# Sheet1.net
KiCad netlist of a schematic drawn in Altium Designer
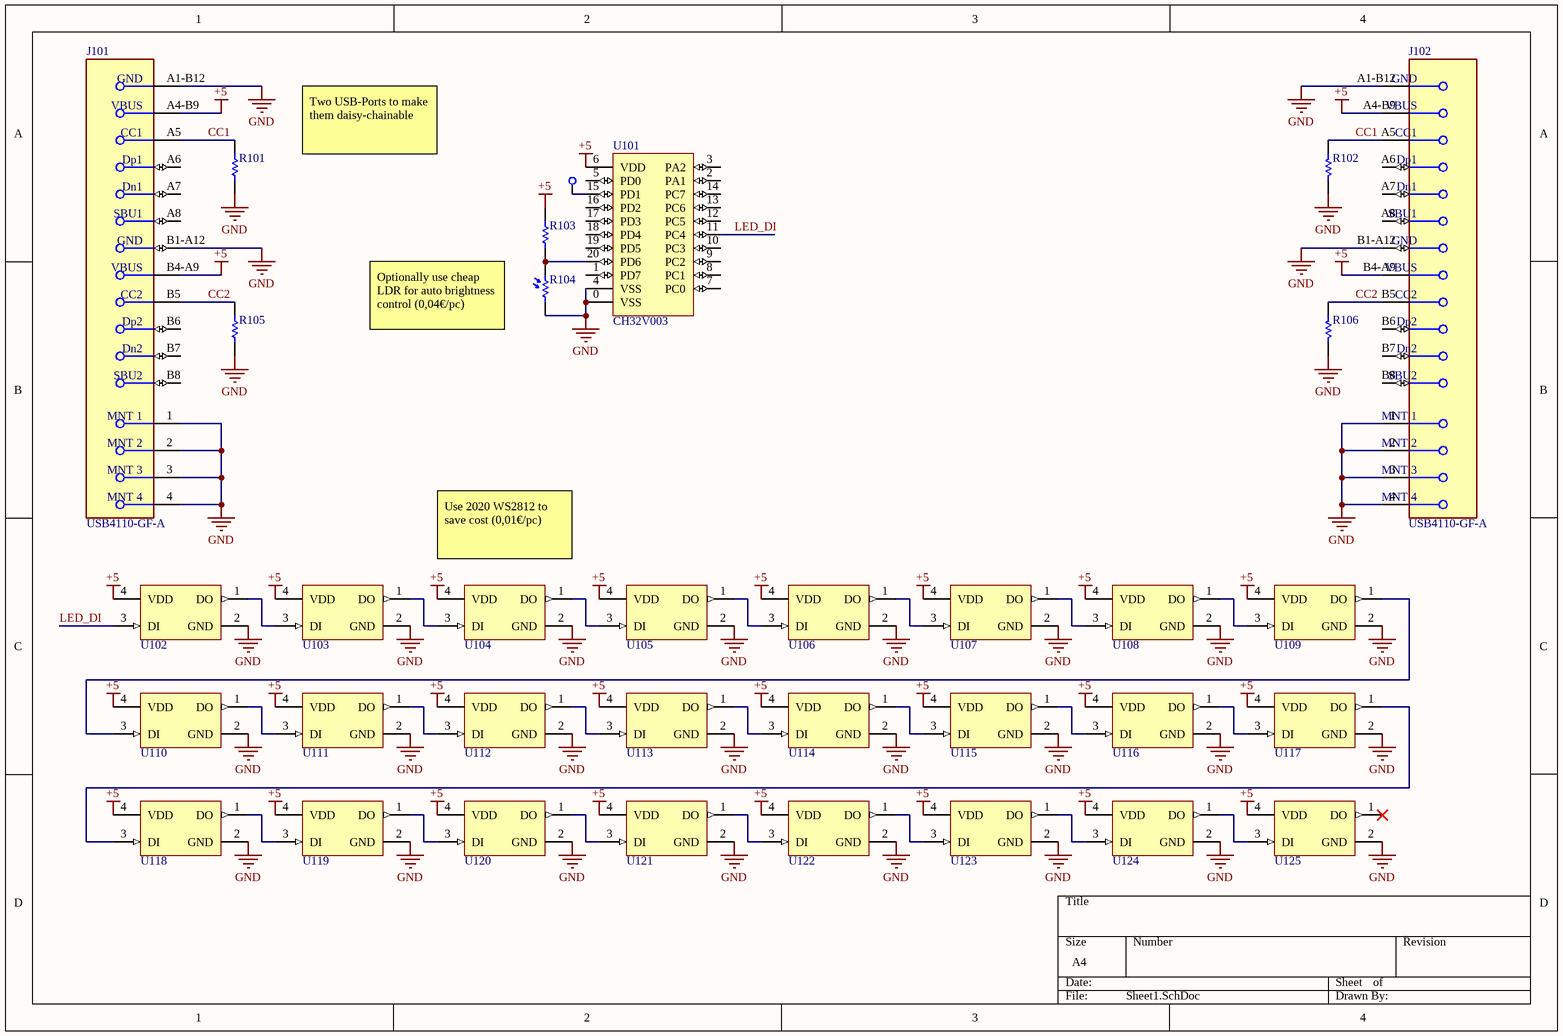
[diagram p0: Sheet1.SchDoc]

(export (version "E")
  (design (tool "Eeschema 10.0.6"))
  (components
    (comp (ref "J101")
      (value "USB4110-GF-A")
      (footprint "FP-USB4110-GF-A-MFG")
      (description "CONN USB 2.0 TYPE-C R/A SMT")
      (fields
        (field (name "OCTOPART") "https://octopart.com/usb4110-gf-a-gct-103941985")
        (field (name "MANUFACTURER") "GCT")
      )
      (libsource (lib "Altium Content Vault") (part "e23f2b38bb3c3f98e683ebab9ede730"))
    )
    (comp (ref "J102")
      (value "USB4110-GF-A")
      (footprint "FP-USB4110-GF-A-MFG")
      (description "CONN USB 2.0 TYPE-C R/A SMT")
      (fields
        (field (name "OCTOPART") "https://octopart.com/usb4110-gf-a-gct-103941985")
        (field (name "MANUFACTURER") "GCT")
      )
      (libsource (lib "") (part "e23f2b38bb3c3f98e683ebab9ede730_1"))
    )
    (comp (ref "R101")
      (value "Resistor")
      (footprint "RESC1608X06N")
      (libsource (lib "Schlib1") (part "R0603"))
    )
    (comp (ref "R102")
      (value "Resistor")
      (footprint "RESC1608X06N")
      (libsource (lib "Schlib1") (part "R0603"))
    )
    (comp (ref "R103")
      (value "Resistor")
      (footprint "RESC1608X06N")
      (libsource (lib "Schlib1") (part "R0603"))
    )
    (comp (ref "R104")
      (value "Photoconductive Resistor")
      (footprint "LDR_5016")
      (libsource (lib "Schlib1") (part "LDR"))
    )
    (comp (ref "R105")
      (value "Resistor")
      (footprint "RESC1608X06N")
      (libsource (lib "Schlib1") (part "R0603"))
    )
    (comp (ref "R106")
      (value "Resistor")
      (footprint "RESC1608X06N")
      (libsource (lib "Schlib1") (part "R0603"))
    )
    (comp (ref "TP101")
      (value "TestPoint")
      (footprint "TestPoint")
      (libsource (lib "Schlib1") (part "TestPoint"))
    )
    (comp (ref "U101")
      (value "CH32V003")
      (footprint "QFN40P300X300X75_HS-21N")
      (libsource (lib "Schlib1") (part "CH32V003F4U6"))
    )
    (comp (ref "U102")
      (value "NOT COMPATIBLE WITH WS2812B")
      (footprint "LED_WS2812-2020")
      (description "Adressable RGB LED")
      (libsource (lib "Schlib1") (part "WS2812_2018"))
    )
    (comp (ref "U103")
      (value "NOT COMPATIBLE WITH WS2812B")
      (footprint "LED_WS2812-2020")
      (description "Adressable RGB LED")
      (libsource (lib "Schlib1") (part "WS2812_2018"))
    )
    (comp (ref "U104")
      (value "NOT COMPATIBLE WITH WS2812B")
      (footprint "LED_WS2812-2020")
      (description "Adressable RGB LED")
      (libsource (lib "Schlib1") (part "WS2812_2018"))
    )
    (comp (ref "U105")
      (value "NOT COMPATIBLE WITH WS2812B")
      (footprint "LED_WS2812-2020")
      (description "Adressable RGB LED")
      (libsource (lib "Schlib1") (part "WS2812_2018"))
    )
    (comp (ref "U106")
      (value "NOT COMPATIBLE WITH WS2812B")
      (footprint "LED_WS2812-2020")
      (description "Adressable RGB LED")
      (libsource (lib "Schlib1") (part "WS2812_2018"))
    )
    (comp (ref "U107")
      (value "NOT COMPATIBLE WITH WS2812B")
      (footprint "LED_WS2812-2020")
      (description "Adressable RGB LED")
      (libsource (lib "Schlib1") (part "WS2812_2018"))
    )
    (comp (ref "U108")
      (value "NOT COMPATIBLE WITH WS2812B")
      (footprint "LED_WS2812-2020")
      (description "Adressable RGB LED")
      (libsource (lib "Schlib1") (part "WS2812_2018"))
    )
    (comp (ref "U109")
      (value "NOT COMPATIBLE WITH WS2812B")
      (footprint "LED_WS2812-2020")
      (description "Adressable RGB LED")
      (libsource (lib "Schlib1") (part "WS2812_2018"))
    )
    (comp (ref "U110")
      (value "NOT COMPATIBLE WITH WS2812B")
      (footprint "LED_WS2812-2020")
      (description "Adressable RGB LED")
      (libsource (lib "Schlib1") (part "WS2812_2018"))
    )
    (comp (ref "U111")
      (value "NOT COMPATIBLE WITH WS2812B")
      (footprint "LED_WS2812-2020")
      (description "Adressable RGB LED")
      (libsource (lib "Schlib1") (part "WS2812_2018"))
    )
    (comp (ref "U112")
      (value "NOT COMPATIBLE WITH WS2812B")
      (footprint "LED_WS2812-2020")
      (description "Adressable RGB LED")
      (libsource (lib "Schlib1") (part "WS2812_2018"))
    )
    (comp (ref "U113")
      (value "NOT COMPATIBLE WITH WS2812B")
      (footprint "LED_WS2812-2020")
      (description "Adressable RGB LED")
      (libsource (lib "Schlib1") (part "WS2812_2018"))
    )
    (comp (ref "U114")
      (value "NOT COMPATIBLE WITH WS2812B")
      (footprint "LED_WS2812-2020")
      (description "Adressable RGB LED")
      (libsource (lib "Schlib1") (part "WS2812_2018"))
    )
    (comp (ref "U115")
      (value "NOT COMPATIBLE WITH WS2812B")
      (footprint "LED_WS2812-2020")
      (description "Adressable RGB LED")
      (libsource (lib "Schlib1") (part "WS2812_2018"))
    )
    (comp (ref "U116")
      (value "NOT COMPATIBLE WITH WS2812B")
      (footprint "LED_WS2812-2020")
      (description "Adressable RGB LED")
      (libsource (lib "Schlib1") (part "WS2812_2018"))
    )
    (comp (ref "U117")
      (value "NOT COMPATIBLE WITH WS2812B")
      (footprint "LED_WS2812-2020")
      (description "Adressable RGB LED")
      (libsource (lib "Schlib1") (part "WS2812_2018"))
    )
    (comp (ref "U118")
      (value "NOT COMPATIBLE WITH WS2812B")
      (footprint "LED_WS2812-2020")
      (description "Adressable RGB LED")
      (libsource (lib "Schlib1") (part "WS2812_2018"))
    )
    (comp (ref "U119")
      (value "NOT COMPATIBLE WITH WS2812B")
      (footprint "LED_WS2812-2020")
      (description "Adressable RGB LED")
      (libsource (lib "Schlib1") (part "WS2812_2018"))
    )
    (comp (ref "U120")
      (value "NOT COMPATIBLE WITH WS2812B")
      (footprint "LED_WS2812-2020")
      (description "Adressable RGB LED")
      (libsource (lib "Schlib1") (part "WS2812_2018"))
    )
    (comp (ref "U121")
      (value "NOT COMPATIBLE WITH WS2812B")
      (footprint "LED_WS2812-2020")
      (description "Adressable RGB LED")
      (libsource (lib "Schlib1") (part "WS2812_2018"))
    )
    (comp (ref "U122")
      (value "NOT COMPATIBLE WITH WS2812B")
      (footprint "LED_WS2812-2020")
      (description "Adressable RGB LED")
      (libsource (lib "Schlib1") (part "WS2812_2018"))
    )
    (comp (ref "U123")
      (value "NOT COMPATIBLE WITH WS2812B")
      (footprint "LED_WS2812-2020")
      (description "Adressable RGB LED")
      (libsource (lib "Schlib1") (part "WS2812_2018"))
    )
    (comp (ref "U124")
      (value "NOT COMPATIBLE WITH WS2812B")
      (footprint "LED_WS2812-2020")
      (description "Adressable RGB LED")
      (libsource (lib "Schlib1") (part "WS2812_2018"))
    )
    (comp (ref "U125")
      (value "NOT COMPATIBLE WITH WS2812B")
      (footprint "LED_WS2812-2020")
      (description "Adressable RGB LED")
      (libsource (lib "Schlib1") (part "WS2812_2018"))
    )
  )
  (nets
    (net (code "1") (name "+5") (class "Default")
      (node (ref "J101") (pin "A4-B9") (pinfunction "VBUS_A4-B9") (pintype "power_in"))
      (node (ref "J101") (pin "B4-A9") (pinfunction "VBUS_B4-A9") (pintype "power_in"))
      (node (ref "J102") (pin "A4-B9") (pinfunction "VBUS_A4-B9") (pintype "power_in"))
      (node (ref "J102") (pin "B4-A9") (pinfunction "VBUS_B4-A9") (pintype "power_in"))
      (node (ref "R103") (pin "2") (pintype "passive"))
      (node (ref "U101") (pin "6") (pinfunction "VDD_6") (pintype "power_in"))
      (node (ref "U102") (pin "4") (pinfunction "VDD_4") (pintype "power_in"))
      (node (ref "U103") (pin "4") (pinfunction "VDD_4") (pintype "power_in"))
      (node (ref "U104") (pin "4") (pinfunction "VDD_4") (pintype "power_in"))
      (node (ref "U105") (pin "4") (pinfunction "VDD_4") (pintype "power_in"))
      (node (ref "U106") (pin "4") (pinfunction "VDD_4") (pintype "power_in"))
      (node (ref "U107") (pin "4") (pinfunction "VDD_4") (pintype "power_in"))
      (node (ref "U108") (pin "4") (pinfunction "VDD_4") (pintype "power_in"))
      (node (ref "U109") (pin "4") (pinfunction "VDD_4") (pintype "power_in"))
      (node (ref "U110") (pin "4") (pinfunction "VDD_4") (pintype "power_in"))
      (node (ref "U111") (pin "4") (pinfunction "VDD_4") (pintype "power_in"))
      (node (ref "U112") (pin "4") (pinfunction "VDD_4") (pintype "power_in"))
      (node (ref "U113") (pin "4") (pinfunction "VDD_4") (pintype "power_in"))
      (node (ref "U114") (pin "4") (pinfunction "VDD_4") (pintype "power_in"))
      (node (ref "U115") (pin "4") (pinfunction "VDD_4") (pintype "power_in"))
      (node (ref "U116") (pin "4") (pinfunction "VDD_4") (pintype "power_in"))
      (node (ref "U117") (pin "4") (pinfunction "VDD_4") (pintype "power_in"))
      (node (ref "U118") (pin "4") (pinfunction "VDD_4") (pintype "power_in"))
      (node (ref "U119") (pin "4") (pinfunction "VDD_4") (pintype "power_in"))
      (node (ref "U120") (pin "4") (pinfunction "VDD_4") (pintype "power_in"))
      (node (ref "U121") (pin "4") (pinfunction "VDD_4") (pintype "power_in"))
      (node (ref "U122") (pin "4") (pinfunction "VDD_4") (pintype "power_in"))
      (node (ref "U123") (pin "4") (pinfunction "VDD_4") (pintype "power_in"))
      (node (ref "U124") (pin "4") (pinfunction "VDD_4") (pintype "power_in"))
      (node (ref "U125") (pin "4") (pinfunction "VDD_4") (pintype "power_in"))
    )
    (net (code "2") (name "/CC1") (class "Default")
      (node (ref "J101") (pin "A5") (pinfunction "CC1_A5") (pintype "power_in"))
      (node (ref "J102") (pin "A5") (pinfunction "CC1_A5") (pintype "power_in"))
      (node (ref "R101") (pin "2") (pintype "passive"))
      (node (ref "R102") (pin "2") (pintype "passive"))
    )
    (net (code "3") (name "/CC2") (class "Default")
      (node (ref "J101") (pin "B5") (pinfunction "CC2_B5") (pintype "power_in"))
      (node (ref "J102") (pin "B5") (pinfunction "CC2_B5") (pintype "power_in"))
      (node (ref "R105") (pin "2") (pintype "passive"))
      (node (ref "R106") (pin "2") (pintype "passive"))
    )
    (net (code "4") (name "/LED_DI") (class "Default")
      (node (ref "U101") (pin "11") (pinfunction "PC4_11") (pintype "bidirectional"))
      (node (ref "U102") (pin "3") (pinfunction "DI_3") (pintype "input"))
    )
    (net (code "5") (name "GND") (class "Default")
      (node (ref "J101") (pin "1") (pinfunction "MNT_1_1") (pintype "passive"))
      (node (ref "J101") (pin "2") (pinfunction "MNT_2_2") (pintype "passive"))
      (node (ref "J101") (pin "3") (pinfunction "MNT_3_3") (pintype "passive"))
      (node (ref "J101") (pin "4") (pinfunction "MNT_4_4") (pintype "passive"))
      (node (ref "J101") (pin "A1-B12") (pinfunction "GND_A1-B12") (pintype "passive"))
      (node (ref "J101") (pin "B1-A12") (pinfunction "GND_B1-A12") (pintype "bidirectional"))
      (node (ref "J102") (pin "1") (pinfunction "MNT_1_1") (pintype "passive"))
      (node (ref "J102") (pin "2") (pinfunction "MNT_2_2") (pintype "passive"))
      (node (ref "J102") (pin "3") (pinfunction "MNT_3_3") (pintype "passive"))
      (node (ref "J102") (pin "4") (pinfunction "MNT_4_4") (pintype "passive"))
      (node (ref "J102") (pin "A1-B12") (pinfunction "GND_A1-B12") (pintype "passive"))
      (node (ref "J102") (pin "B1-A12") (pinfunction "GND_B1-A12") (pintype "bidirectional"))
      (node (ref "R101") (pin "1") (pintype "passive"))
      (node (ref "R102") (pin "1") (pintype "passive"))
      (node (ref "R104") (pin "1") (pintype "passive"))
      (node (ref "R105") (pin "1") (pintype "passive"))
      (node (ref "R106") (pin "1") (pintype "passive"))
      (node (ref "U101") (pin "0") (pinfunction "VSS_0") (pintype "power_in"))
      (node (ref "U101") (pin "4") (pinfunction "VSS_4") (pintype "power_in"))
      (node (ref "U102") (pin "2") (pinfunction "GND_2") (pintype "power_in"))
      (node (ref "U103") (pin "2") (pinfunction "GND_2") (pintype "power_in"))
      (node (ref "U104") (pin "2") (pinfunction "GND_2") (pintype "power_in"))
      (node (ref "U105") (pin "2") (pinfunction "GND_2") (pintype "power_in"))
      (node (ref "U106") (pin "2") (pinfunction "GND_2") (pintype "power_in"))
      (node (ref "U107") (pin "2") (pinfunction "GND_2") (pintype "power_in"))
      (node (ref "U108") (pin "2") (pinfunction "GND_2") (pintype "power_in"))
      (node (ref "U109") (pin "2") (pinfunction "GND_2") (pintype "power_in"))
      (node (ref "U110") (pin "2") (pinfunction "GND_2") (pintype "power_in"))
      (node (ref "U111") (pin "2") (pinfunction "GND_2") (pintype "power_in"))
      (node (ref "U112") (pin "2") (pinfunction "GND_2") (pintype "power_in"))
      (node (ref "U113") (pin "2") (pinfunction "GND_2") (pintype "power_in"))
      (node (ref "U114") (pin "2") (pinfunction "GND_2") (pintype "power_in"))
      (node (ref "U115") (pin "2") (pinfunction "GND_2") (pintype "power_in"))
      (node (ref "U116") (pin "2") (pinfunction "GND_2") (pintype "power_in"))
      (node (ref "U117") (pin "2") (pinfunction "GND_2") (pintype "power_in"))
      (node (ref "U118") (pin "2") (pinfunction "GND_2") (pintype "power_in"))
      (node (ref "U119") (pin "2") (pinfunction "GND_2") (pintype "power_in"))
      (node (ref "U120") (pin "2") (pinfunction "GND_2") (pintype "power_in"))
      (node (ref "U121") (pin "2") (pinfunction "GND_2") (pintype "power_in"))
      (node (ref "U122") (pin "2") (pinfunction "GND_2") (pintype "power_in"))
      (node (ref "U123") (pin "2") (pinfunction "GND_2") (pintype "power_in"))
      (node (ref "U124") (pin "2") (pinfunction "GND_2") (pintype "power_in"))
      (node (ref "U125") (pin "2") (pinfunction "GND_2") (pintype "power_in"))
    )
    (net (code "6") (name "Net-(U101-PD1)") (class "Default")
      (node (ref "TP101") (pin "TP") (pinfunction "TP_TP") (pintype "passive"))
      (node (ref "U101") (pin "15") (pinfunction "PD1_15") (pintype "bidirectional"))
    )
    (net (code "7") (name "Net-(U101-PD6)") (class "Default")
      (node (ref "R103") (pin "1") (pintype "passive"))
      (node (ref "R104") (pin "2") (pintype "passive"))
      (node (ref "U101") (pin "20") (pinfunction "PD6_20") (pintype "bidirectional"))
    )
    (net (code "8") (name "Net-(U102-DO)") (class "Default")
      (node (ref "U102") (pin "1") (pinfunction "DO_1") (pintype "output"))
      (node (ref "U103") (pin "3") (pinfunction "DI_3") (pintype "input"))
    )
    (net (code "9") (name "Net-(U103-DO)") (class "Default")
      (node (ref "U103") (pin "1") (pinfunction "DO_1") (pintype "output"))
      (node (ref "U104") (pin "3") (pinfunction "DI_3") (pintype "input"))
    )
    (net (code "10") (name "Net-(U104-DO)") (class "Default")
      (node (ref "U104") (pin "1") (pinfunction "DO_1") (pintype "output"))
      (node (ref "U105") (pin "3") (pinfunction "DI_3") (pintype "input"))
    )
    (net (code "11") (name "Net-(U105-DO)") (class "Default")
      (node (ref "U105") (pin "1") (pinfunction "DO_1") (pintype "output"))
      (node (ref "U106") (pin "3") (pinfunction "DI_3") (pintype "input"))
    )
    (net (code "12") (name "Net-(U106-DO)") (class "Default")
      (node (ref "U106") (pin "1") (pinfunction "DO_1") (pintype "output"))
      (node (ref "U107") (pin "3") (pinfunction "DI_3") (pintype "input"))
    )
    (net (code "13") (name "Net-(U107-DO)") (class "Default")
      (node (ref "U107") (pin "1") (pinfunction "DO_1") (pintype "output"))
      (node (ref "U108") (pin "3") (pinfunction "DI_3") (pintype "input"))
    )
    (net (code "14") (name "Net-(U108-DO)") (class "Default")
      (node (ref "U108") (pin "1") (pinfunction "DO_1") (pintype "output"))
      (node (ref "U109") (pin "3") (pinfunction "DI_3") (pintype "input"))
    )
    (net (code "15") (name "Net-(U109-DO)") (class "Default")
      (node (ref "U109") (pin "1") (pinfunction "DO_1") (pintype "output"))
      (node (ref "U110") (pin "3") (pinfunction "DI_3") (pintype "input"))
    )
    (net (code "16") (name "Net-(U110-DO)") (class "Default")
      (node (ref "U110") (pin "1") (pinfunction "DO_1") (pintype "output"))
      (node (ref "U111") (pin "3") (pinfunction "DI_3") (pintype "input"))
    )
    (net (code "17") (name "Net-(U111-DO)") (class "Default")
      (node (ref "U111") (pin "1") (pinfunction "DO_1") (pintype "output"))
      (node (ref "U112") (pin "3") (pinfunction "DI_3") (pintype "input"))
    )
    (net (code "18") (name "Net-(U112-DO)") (class "Default")
      (node (ref "U112") (pin "1") (pinfunction "DO_1") (pintype "output"))
      (node (ref "U113") (pin "3") (pinfunction "DI_3") (pintype "input"))
    )
    (net (code "19") (name "Net-(U113-DO)") (class "Default")
      (node (ref "U113") (pin "1") (pinfunction "DO_1") (pintype "output"))
      (node (ref "U114") (pin "3") (pinfunction "DI_3") (pintype "input"))
    )
    (net (code "20") (name "Net-(U114-DO)") (class "Default")
      (node (ref "U114") (pin "1") (pinfunction "DO_1") (pintype "output"))
      (node (ref "U115") (pin "3") (pinfunction "DI_3") (pintype "input"))
    )
    (net (code "21") (name "Net-(U115-DO)") (class "Default")
      (node (ref "U115") (pin "1") (pinfunction "DO_1") (pintype "output"))
      (node (ref "U116") (pin "3") (pinfunction "DI_3") (pintype "input"))
    )
    (net (code "22") (name "Net-(U116-DO)") (class "Default")
      (node (ref "U116") (pin "1") (pinfunction "DO_1") (pintype "output"))
      (node (ref "U117") (pin "3") (pinfunction "DI_3") (pintype "input"))
    )
    (net (code "23") (name "Net-(U117-DO)") (class "Default")
      (node (ref "U117") (pin "1") (pinfunction "DO_1") (pintype "output"))
      (node (ref "U118") (pin "3") (pinfunction "DI_3") (pintype "input"))
    )
    (net (code "24") (name "Net-(U118-DO)") (class "Default")
      (node (ref "U118") (pin "1") (pinfunction "DO_1") (pintype "output"))
      (node (ref "U119") (pin "3") (pinfunction "DI_3") (pintype "input"))
    )
    (net (code "25") (name "Net-(U119-DO)") (class "Default")
      (node (ref "U119") (pin "1") (pinfunction "DO_1") (pintype "output"))
      (node (ref "U120") (pin "3") (pinfunction "DI_3") (pintype "input"))
    )
    (net (code "26") (name "Net-(U120-DO)") (class "Default")
      (node (ref "U120") (pin "1") (pinfunction "DO_1") (pintype "output"))
      (node (ref "U121") (pin "3") (pinfunction "DI_3") (pintype "input"))
    )
    (net (code "27") (name "Net-(U121-DO)") (class "Default")
      (node (ref "U121") (pin "1") (pinfunction "DO_1") (pintype "output"))
      (node (ref "U122") (pin "3") (pinfunction "DI_3") (pintype "input"))
    )
    (net (code "28") (name "Net-(U122-DO)") (class "Default")
      (node (ref "U122") (pin "1") (pinfunction "DO_1") (pintype "output"))
      (node (ref "U123") (pin "3") (pinfunction "DI_3") (pintype "input"))
    )
    (net (code "29") (name "Net-(U123-DO)") (class "Default")
      (node (ref "U123") (pin "1") (pinfunction "DO_1") (pintype "output"))
      (node (ref "U124") (pin "3") (pinfunction "DI_3") (pintype "input"))
    )
    (net (code "30") (name "Net-(U124-DO)") (class "Default")
      (node (ref "U124") (pin "1") (pinfunction "DO_1") (pintype "output"))
      (node (ref "U125") (pin "3") (pinfunction "DI_3") (pintype "input"))
    )
    (net (code "31") (name "unconnected-(J101-Dn1-PadA7)") (class "Default")
      (node (ref "J101") (pin "A7") (pinfunction "Dn1_A7") (pintype "bidirectional"))
    )
    (net (code "32") (name "unconnected-(J101-Dn2-PadB7)") (class "Default")
      (node (ref "J101") (pin "B7") (pinfunction "Dn2_B7") (pintype "bidirectional"))
    )
    (net (code "33") (name "unconnected-(J101-Dp1-PadA6)") (class "Default")
      (node (ref "J101") (pin "A6") (pinfunction "Dp1_A6") (pintype "bidirectional"))
    )
    (net (code "34") (name "unconnected-(J101-Dp2-PadB6)") (class "Default")
      (node (ref "J101") (pin "B6") (pinfunction "Dp2_B6") (pintype "bidirectional"))
    )
    (net (code "35") (name "unconnected-(J101-SBU1-PadA8)") (class "Default")
      (node (ref "J101") (pin "A8") (pinfunction "SBU1_A8") (pintype "bidirectional"))
    )
    (net (code "36") (name "unconnected-(J101-SBU2-PadB8)") (class "Default")
      (node (ref "J101") (pin "B8") (pinfunction "SBU2_B8") (pintype "bidirectional"))
    )
    (net (code "37") (name "unconnected-(J102-Dn1-PadA7)") (class "Default")
      (node (ref "J102") (pin "A7") (pinfunction "Dn1_A7") (pintype "bidirectional"))
    )
    (net (code "38") (name "unconnected-(J102-Dn2-PadB7)") (class "Default")
      (node (ref "J102") (pin "B7") (pinfunction "Dn2_B7") (pintype "bidirectional"))
    )
    (net (code "39") (name "unconnected-(J102-Dp1-PadA6)") (class "Default")
      (node (ref "J102") (pin "A6") (pinfunction "Dp1_A6") (pintype "bidirectional"))
    )
    (net (code "40") (name "unconnected-(J102-Dp2-PadB6)") (class "Default")
      (node (ref "J102") (pin "B6") (pinfunction "Dp2_B6") (pintype "bidirectional"))
    )
    (net (code "41") (name "unconnected-(J102-SBU1-PadA8)") (class "Default")
      (node (ref "J102") (pin "A8") (pinfunction "SBU1_A8") (pintype "bidirectional"))
    )
    (net (code "42") (name "unconnected-(J102-SBU2-PadB8)") (class "Default")
      (node (ref "J102") (pin "B8") (pinfunction "SBU2_B8") (pintype "bidirectional"))
    )
    (net (code "43") (name "unconnected-(U101-PA1-Pad2)") (class "Default")
      (node (ref "U101") (pin "2") (pinfunction "PA1_2") (pintype "bidirectional"))
    )
    (net (code "44") (name "unconnected-(U101-PA2-Pad3)") (class "Default")
      (node (ref "U101") (pin "3") (pinfunction "PA2_3") (pintype "bidirectional"))
    )
    (net (code "45") (name "unconnected-(U101-PC0-Pad7)") (class "Default")
      (node (ref "U101") (pin "7") (pinfunction "PC0_7") (pintype "bidirectional"))
    )
    (net (code "46") (name "unconnected-(U101-PC1-Pad8)") (class "Default")
      (node (ref "U101") (pin "8") (pinfunction "PC1_8") (pintype "bidirectional"))
    )
    (net (code "47") (name "unconnected-(U101-PC2-Pad9)") (class "Default")
      (node (ref "U101") (pin "9") (pinfunction "PC2_9") (pintype "bidirectional"))
    )
    (net (code "48") (name "unconnected-(U101-PC3-Pad10)") (class "Default")
      (node (ref "U101") (pin "10") (pinfunction "PC3_10") (pintype "bidirectional"))
    )
    (net (code "49") (name "unconnected-(U101-PC5-Pad12)") (class "Default")
      (node (ref "U101") (pin "12") (pinfunction "PC5_12") (pintype "bidirectional"))
    )
    (net (code "50") (name "unconnected-(U101-PC6-Pad13)") (class "Default")
      (node (ref "U101") (pin "13") (pinfunction "PC6_13") (pintype "bidirectional"))
    )
    (net (code "51") (name "unconnected-(U101-PC7-Pad14)") (class "Default")
      (node (ref "U101") (pin "14") (pinfunction "PC7_14") (pintype "bidirectional"))
    )
    (net (code "52") (name "unconnected-(U101-PD0-Pad5)") (class "Default")
      (node (ref "U101") (pin "5") (pinfunction "PD0_5") (pintype "bidirectional"))
    )
    (net (code "53") (name "unconnected-(U101-PD2-Pad16)") (class "Default")
      (node (ref "U101") (pin "16") (pinfunction "PD2_16") (pintype "bidirectional"))
    )
    (net (code "54") (name "unconnected-(U101-PD3-Pad17)") (class "Default")
      (node (ref "U101") (pin "17") (pinfunction "PD3_17") (pintype "bidirectional"))
    )
    (net (code "55") (name "unconnected-(U101-PD4-Pad18)") (class "Default")
      (node (ref "U101") (pin "18") (pinfunction "PD4_18") (pintype "bidirectional"))
    )
    (net (code "56") (name "unconnected-(U101-PD5-Pad19)") (class "Default")
      (node (ref "U101") (pin "19") (pinfunction "PD5_19") (pintype "bidirectional"))
    )
    (net (code "57") (name "unconnected-(U101-PD7-Pad1)") (class "Default")
      (node (ref "U101") (pin "1") (pinfunction "PD7_1") (pintype "bidirectional"))
    )
    (net (code "58") (name "unconnected-(U125-DO-Pad1)") (class "Default")
      (node (ref "U125") (pin "1") (pinfunction "DO_1") (pintype "output+no_connect"))
    )
  )
)
